# xover.net
KiCad netlist of a schematic drawn in Altium Designer
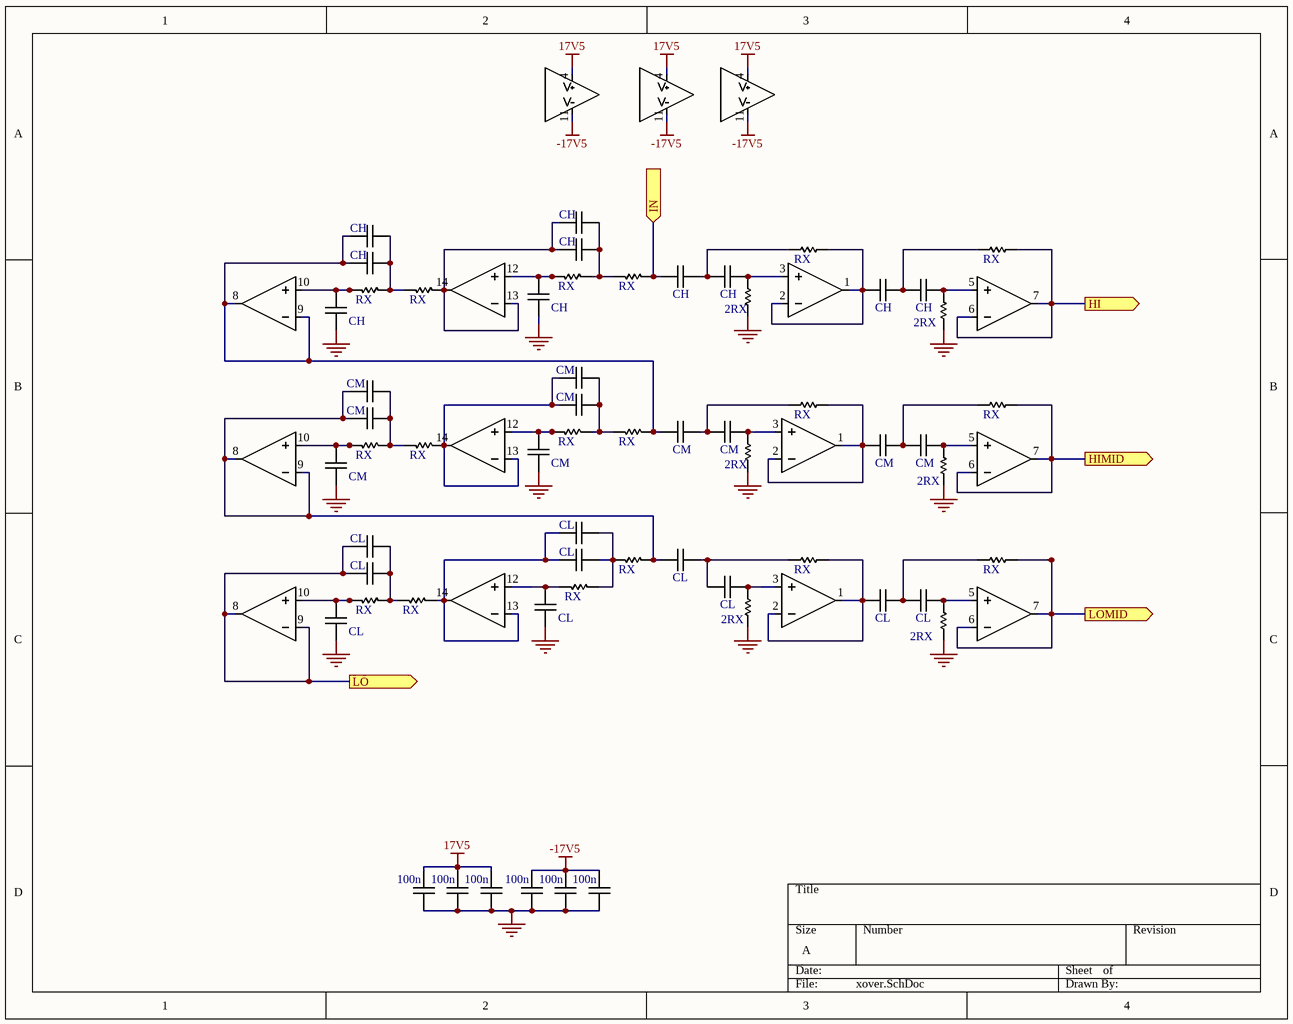
[diagram p0: xover.SchDoc]

(export (version "E")
  (design (tool "Eeschema 10.0.6"))
  (components
    (comp (ref "C136")
      (value "CH")
      (footprint "0805")
      (fields (field (name "PARTNUMBER") "NMC0805NPO562J50TRPLPF"))
      (libsource (lib "mix") (part "CAP"))
    )
    (comp (ref "C139")
      (value "CH")
      (footprint "0805")
      (fields (field (name "PARTNUMBER") "NMC0805NPO562J50TRPLPF"))
      (libsource (lib "mix") (part "CAP"))
    )
    (comp (ref "C142")
      (value "CH")
      (footprint "0805")
      (fields (field (name "PARTNUMBER") "NMC0805NPO562J50TRPLPF"))
      (libsource (lib "mix") (part "CAP"))
    )
    (comp (ref "C143")
      (value "CH")
      (footprint "0805")
      (fields (field (name "PARTNUMBER") "NMC0805NPO562J50TRPLPF"))
      (libsource (lib "mix") (part "CAP"))
    )
    (comp (ref "C145")
      (value "CH")
      (footprint "0805")
      (fields (field (name "PARTNUMBER") "NMC0805NPO562J50TRPLPF"))
      (libsource (lib "mix") (part "CAP"))
    )
    (comp (ref "C148")
      (value "CH")
      (footprint "0805")
      (fields (field (name "PARTNUMBER") "NMC0805NPO562J50TRPLPF"))
      (libsource (lib "mix") (part "CAP"))
    )
    (comp (ref "C149")
      (value "CH")
      (footprint "0805")
      (fields (field (name "PARTNUMBER") "NMC0805NPO562J50TRPLPF"))
      (libsource (lib "mix") (part "CAP"))
    )
    (comp (ref "C150")
      (value "CH")
      (footprint "0805")
      (fields (field (name "PARTNUMBER") "NMC0805NPO562J50TRPLPF"))
      (libsource (lib "mix") (part "CAP"))
    )
    (comp (ref "C152")
      (value "CH")
      (footprint "0805")
      (fields (field (name "PARTNUMBER") "NMC0805NPO562J50TRPLPF"))
      (libsource (lib "mix") (part "CAP"))
    )
    (comp (ref "C154")
      (value "CH")
      (footprint "0805")
      (fields (field (name "PARTNUMBER") "NMC0805NPO562J50TRPLPF"))
      (libsource (lib "mix") (part "CAP"))
    )
    (comp (ref "C155")
      (value "CM")
      (footprint "0805")
      (fields (field (name "PARTNUMBER") "C0805C223J5JACTU"))
      (libsource (lib "mix") (part "CAP"))
    )
    (comp (ref "C158")
      (value "CM")
      (footprint "0805")
      (fields (field (name "PARTNUMBER") "C0805C223J5JACTU"))
      (libsource (lib "mix") (part "CAP"))
    )
    (comp (ref "C162")
      (value "CM")
      (footprint "0805")
      (fields (field (name "PARTNUMBER") "C0805C223J5JACTU"))
      (libsource (lib "mix") (part "CAP"))
    )
    (comp (ref "C163")
      (value "CM")
      (footprint "0805")
      (fields (field (name "PARTNUMBER") "C0805C223J5JACTU"))
      (libsource (lib "mix") (part "CAP"))
    )
    (comp (ref "C166")
      (value "CM")
      (footprint "0805")
      (fields (field (name "PARTNUMBER") "C0805C223J5JACTU"))
      (libsource (lib "mix") (part "CAP"))
    )
    (comp (ref "C170")
      (value "CM")
      (footprint "0805")
      (fields (field (name "PARTNUMBER") "C0805C223J5JACTU"))
      (libsource (lib "mix") (part "CAP"))
    )
    (comp (ref "C171")
      (value "CM")
      (footprint "0805")
      (fields (field (name "PARTNUMBER") "C0805C223J5JACTU"))
      (libsource (lib "mix") (part "CAP"))
    )
    (comp (ref "C172")
      (value "CM")
      (footprint "0805")
      (fields (field (name "PARTNUMBER") "C0805C223J5JACTU"))
      (libsource (lib "mix") (part "CAP"))
    )
    (comp (ref "C174")
      (value "CM")
      (footprint "0805")
      (fields (field (name "PARTNUMBER") "C0805C223J5JACTU"))
      (libsource (lib "mix") (part "CAP"))
    )
    (comp (ref "C176")
      (value "CM")
      (footprint "0805")
      (fields (field (name "PARTNUMBER") "C0805C223J5JACTU"))
      (libsource (lib "mix") (part "CAP"))
    )
    (comp (ref "C180")
      (value "CL")
      (footprint "0805")
      (fields (field (name "PARTNUMBER") "NMC0805X7R823J50TRPF"))
      (libsource (lib "mix") (part "CAP"))
    )
    (comp (ref "C182")
      (value "CL")
      (footprint "0805")
      (fields (field (name "PARTNUMBER") "NMC0805X7R823J50TRPF"))
      (libsource (lib "mix") (part "CAP"))
    )
    (comp (ref "C185")
      (value "CL")
      (footprint "0805")
      (fields (field (name "PARTNUMBER") "NMC0805X7R823J50TRPF"))
      (libsource (lib "mix") (part "CAP"))
    )
    (comp (ref "C186")
      (value "CL")
      (footprint "0805")
      (fields (field (name "PARTNUMBER") "NMC0805X7R823J50TRPF"))
      (libsource (lib "mix") (part "CAP"))
    )
    (comp (ref "C188")
      (value "CL")
      (footprint "0805")
      (fields (field (name "PARTNUMBER") "NMC0805X7R823J50TRPF"))
      (libsource (lib "mix") (part "CAP"))
    )
    (comp (ref "C192")
      (value "CL")
      (footprint "0805")
      (fields (field (name "PARTNUMBER") "NMC0805X7R823J50TRPF"))
      (libsource (lib "mix") (part "CAP"))
    )
    (comp (ref "C193")
      (value "CL")
      (footprint "0805")
      (fields (field (name "PARTNUMBER") "NMC0805X7R823J50TRPF"))
      (libsource (lib "mix") (part "CAP"))
    )
    (comp (ref "C194")
      (value "CL")
      (footprint "0805")
      (fields (field (name "PARTNUMBER") "NMC0805X7R823J50TRPF"))
      (libsource (lib "mix") (part "CAP"))
    )
    (comp (ref "C198")
      (value "CL")
      (footprint "0805")
      (fields (field (name "PARTNUMBER") "NMC0805X7R823J50TRPF"))
      (libsource (lib "mix") (part "CAP"))
    )
    (comp (ref "C200")
      (value "CL")
      (footprint "0805")
      (fields (field (name "PARTNUMBER") "NMC0805X7R823J50TRPF"))
      (libsource (lib "mix") (part "CAP"))
    )
    (comp (ref "C204")
      (value "100n")
      (footprint "0805")
      (fields (field (name "PARTNUMBER") "C0805C104K1RAC7800"))
      (libsource (lib "mix") (part "CAP"))
    )
    (comp (ref "C206")
      (value "100n")
      (footprint "0805")
      (fields (field (name "PARTNUMBER") "C0805C104K1RAC7800"))
      (libsource (lib "mix") (part "CAP"))
    )
    (comp (ref "C211")
      (value "100n")
      (footprint "0805")
      (fields (field (name "PARTNUMBER") "C0805C104K1RAC7800"))
      (libsource (lib "mix") (part "CAP"))
    )
    (comp (ref "C213")
      (value "100n")
      (footprint "0805")
      (fields (field (name "PARTNUMBER") "C0805C104K1RAC7800"))
      (libsource (lib "mix") (part "CAP"))
    )
    (comp (ref "C217")
      (value "100n")
      (footprint "0805")
      (fields (field (name "PARTNUMBER") "C0805C104K1RAC7800"))
      (libsource (lib "mix") (part "CAP"))
    )
    (comp (ref "C218")
      (value "100n")
      (footprint "0805")
      (fields (field (name "PARTNUMBER") "C0805C104K1RAC7800"))
      (libsource (lib "mix") (part "CAP"))
    )
    (comp (ref "R154")
      (value "RX")
      (footprint "0805")
      (fields (field (name "PARTNUMBER") "ERJ-6ENF4871V"))
      (libsource (lib "mix") (part "RES"))
    )
    (comp (ref "R156")
      (value "RX")
      (footprint "0805")
      (fields (field (name "PARTNUMBER") "ERJ-6ENF4871V"))
      (libsource (lib "mix") (part "RES"))
    )
    (comp (ref "R158")
      (value "RX")
      (footprint "0805")
      (fields (field (name "PARTNUMBER") "ERJ-6ENF4871V"))
      (libsource (lib "mix") (part "RES"))
    )
    (comp (ref "R159")
      (value "RX")
      (footprint "0805")
      (fields (field (name "PARTNUMBER") "ERJ-6ENF4871V"))
      (libsource (lib "mix") (part "RES"))
    )
    (comp (ref "R162")
      (value "RX")
      (footprint "0805")
      (fields (field (name "PARTNUMBER") "ERJ-6ENF4871V"))
      (libsource (lib "mix") (part "RES"))
    )
    (comp (ref "R163")
      (value "RX")
      (footprint "0805")
      (fields (field (name "PARTNUMBER") "ERJ-6ENF4871V"))
      (libsource (lib "mix") (part "RES"))
    )
    (comp (ref "R165")
      (value "2RX")
      (footprint "0805")
      (fields (field (name "PARTNUMBER") "ERJ-6ENF9761V"))
      (libsource (lib "mix") (part "RES"))
    )
    (comp (ref "R167")
      (value "2RX")
      (footprint "0805")
      (fields (field (name "PARTNUMBER") "ERJ-6ENF9761V"))
      (libsource (lib "mix") (part "RES"))
    )
    (comp (ref "R169")
      (value "RX")
      (footprint "0805")
      (fields (field (name "PARTNUMBER") "ERJ-6ENF4871V"))
      (libsource (lib "mix") (part "RES"))
    )
    (comp (ref "R170")
      (value "RX")
      (footprint "0805")
      (fields (field (name "PARTNUMBER") "ERJ-6ENF4871V"))
      (libsource (lib "mix") (part "RES"))
    )
    (comp (ref "R172")
      (value "RX")
      (footprint "0805")
      (fields (field (name "PARTNUMBER") "ERJ-6ENF4871V"))
      (libsource (lib "mix") (part "RES"))
    )
    (comp (ref "R176")
      (value "RX")
      (footprint "0805")
      (fields (field (name "PARTNUMBER") "ERJ-6ENF4871V"))
      (libsource (lib "mix") (part "RES"))
    )
    (comp (ref "R180")
      (value "RX")
      (footprint "0805")
      (fields (field (name "PARTNUMBER") "ERJ-6ENF4871V"))
      (libsource (lib "mix") (part "RES"))
    )
    (comp (ref "R181")
      (value "RX")
      (footprint "0805")
      (fields (field (name "PARTNUMBER") "ERJ-6ENF4871V"))
      (libsource (lib "mix") (part "RES"))
    )
    (comp (ref "R183")
      (value "2RX")
      (footprint "0805")
      (fields (field (name "PARTNUMBER") "ERJ-6ENF9761V"))
      (libsource (lib "mix") (part "RES"))
    )
    (comp (ref "R186")
      (value "2RX")
      (footprint "0805")
      (fields (field (name "PARTNUMBER") "ERJ-6ENF9761V"))
      (libsource (lib "mix") (part "RES"))
    )
    (comp (ref "R189")
      (value "RX")
      (footprint "0805")
      (fields (field (name "PARTNUMBER") "ERJ-6ENF4871V"))
      (libsource (lib "mix") (part "RES"))
    )
    (comp (ref "R191")
      (value "RX")
      (footprint "0805")
      (fields (field (name "PARTNUMBER") "ERJ-6ENF4871V"))
      (libsource (lib "mix") (part "RES"))
    )
    (comp (ref "R194")
      (value "RX")
      (footprint "0805")
      (fields (field (name "PARTNUMBER") "ERJ-6ENF4871V"))
      (libsource (lib "mix") (part "RES"))
    )
    (comp (ref "R195")
      (value "RX")
      (footprint "0805")
      (fields (field (name "PARTNUMBER") "ERJ-6ENF4871V"))
      (libsource (lib "mix") (part "RES"))
    )
    (comp (ref "R198")
      (value "RX")
      (footprint "0805")
      (fields (field (name "PARTNUMBER") "ERJ-6ENF4871V"))
      (libsource (lib "mix") (part "RES"))
    )
    (comp (ref "R199")
      (value "RX")
      (footprint "0805")
      (fields (field (name "PARTNUMBER") "ERJ-6ENF4871V"))
      (libsource (lib "mix") (part "RES"))
    )
    (comp (ref "R203")
      (value "2RX")
      (footprint "0805")
      (fields (field (name "PARTNUMBER") "ERJ-6ENF9761V"))
      (libsource (lib "mix") (part "RES"))
    )
    (comp (ref "R205")
      (value "2RX")
      (footprint "0805")
      (fields (field (name "PARTNUMBER") "ERJ-6ENF9761V"))
      (libsource (lib "mix") (part "RES"))
    )
    (comp (ref "U27")
      (value "OPA16X4")
      (footprint "SOIC127P600X175-14M")
      (fields (field (name "PARTNUMBER") "OPA1664AIDR"))
      (libsource (lib "") (part "OPA16X4_1"))
    )
    (comp (ref "U28")
      (value "OPA16X4")
      (footprint "SOIC127P600X175-14M")
      (fields (field (name "PARTNUMBER") "OPA1664AIDR"))
      (libsource (lib "") (part "OPA16X4_1"))
    )
    (comp (ref "U29")
      (value "OPA16X4")
      (footprint "SOIC127P600X175-14M")
      (fields (field (name "PARTNUMBER") "OPA1664AIDR"))
      (libsource (lib "mix") (part "OPA16X4"))
    )
  )
  (nets
    (net (code "1") (name "-17V5") (class "Default")
      (node (ref "C204") (pin "1") (pinfunction "1_1") (pintype "passive"))
      (node (ref "C206") (pin "1") (pinfunction "1_1") (pintype "passive"))
      (node (ref "C217") (pin "1") (pinfunction "1_1") (pintype "passive"))
      (node (ref "U27") (pin "11") (pinfunction "V-_11") (pintype "passive"))
      (node (ref "U28") (pin "11") (pinfunction "V-_11") (pintype "passive"))
      (node (ref "U29") (pin "11") (pinfunction "V-_11") (pintype "passive"))
    )
    (net (code "2") (name "/HI") (class "Default")
      (node (ref "R163") (pin "1") (pinfunction "1_1") (pintype "passive"))
      (node (ref "U27") (pin "6") (pinfunction "IN_B-_6") (pintype "passive"))
      (node (ref "U27") (pin "7") (pinfunction "OUT_B_7") (pintype "passive"))
    )
    (net (code "3") (name "/HIMID") (class "Default")
      (node (ref "R181") (pin "1") (pinfunction "1_1") (pintype "passive"))
      (node (ref "U28") (pin "6") (pinfunction "IN_B-_6") (pintype "passive"))
      (node (ref "U28") (pin "7") (pinfunction "OUT_B_7") (pintype "passive"))
    )
    (net (code "4") (name "/IN") (class "Default")
      (node (ref "C142") (pin "1") (pinfunction "1_1") (pintype "passive"))
      (node (ref "R154") (pin "1") (pinfunction "1_1") (pintype "passive"))
    )
    (net (code "5") (name "/LO") (class "Default")
      (node (ref "C182") (pin "1") (pinfunction "1_1") (pintype "passive"))
      (node (ref "C188") (pin "1") (pinfunction "1_1") (pintype "passive"))
      (node (ref "U29") (pin "8") (pinfunction "OUT_C_8") (pintype "passive"))
      (node (ref "U29") (pin "9") (pinfunction "IN_C-_9") (pintype "passive"))
    )
    (net (code "6") (name "/LOMID") (class "Default")
      (node (ref "R199") (pin "1") (pinfunction "1_1") (pintype "passive"))
      (node (ref "U29") (pin "6") (pinfunction "IN_B-_6") (pintype "passive"))
      (node (ref "U29") (pin "7") (pinfunction "OUT_B_7") (pintype "passive"))
    )
    (net (code "7") (name "17V5") (class "Default")
      (node (ref "C211") (pin "1") (pinfunction "1_1") (pintype "passive"))
      (node (ref "C213") (pin "1") (pinfunction "1_1") (pintype "passive"))
      (node (ref "C218") (pin "1") (pinfunction "1_1") (pintype "passive"))
      (node (ref "U27") (pin "4") (pinfunction "V+_4") (pintype "passive"))
      (node (ref "U28") (pin "4") (pinfunction "V+_4") (pintype "passive"))
      (node (ref "U29") (pin "4") (pinfunction "V+_4") (pintype "passive"))
    )
    (net (code "8") (name "GND") (class "Default")
      (node (ref "C152") (pin "1") (pinfunction "1_1") (pintype "passive"))
      (node (ref "C154") (pin "1") (pinfunction "1_1") (pintype "passive"))
      (node (ref "C174") (pin "1") (pinfunction "1_1") (pintype "passive"))
      (node (ref "C176") (pin "1") (pinfunction "1_1") (pintype "passive"))
      (node (ref "C198") (pin "1") (pinfunction "1_1") (pintype "passive"))
      (node (ref "C200") (pin "1") (pinfunction "1_1") (pintype "passive"))
      (node (ref "C204") (pin "2") (pinfunction "2_2") (pintype "passive"))
      (node (ref "C206") (pin "2") (pinfunction "2_2") (pintype "passive"))
      (node (ref "C211") (pin "2") (pinfunction "2_2") (pintype "passive"))
      (node (ref "C213") (pin "2") (pinfunction "2_2") (pintype "passive"))
      (node (ref "C217") (pin "2") (pinfunction "2_2") (pintype "passive"))
      (node (ref "C218") (pin "2") (pinfunction "2_2") (pintype "passive"))
      (node (ref "R165") (pin "2") (pinfunction "2_2") (pintype "passive"))
      (node (ref "R167") (pin "1") (pinfunction "1_1") (pintype "passive"))
      (node (ref "R183") (pin "2") (pinfunction "2_2") (pintype "passive"))
      (node (ref "R186") (pin "1") (pinfunction "1_1") (pintype "passive"))
      (node (ref "R203") (pin "2") (pinfunction "2_2") (pintype "passive"))
      (node (ref "R205") (pin "1") (pinfunction "1_1") (pintype "passive"))
    )
    (net (code "9") (name "Net-(C136-Pad2)") (class "Default")
      (node (ref "C136") (pin "2") (pinfunction "2_2") (pintype "passive"))
      (node (ref "C143") (pin "2") (pinfunction "2_2") (pintype "passive"))
      (node (ref "R154") (pin "2") (pinfunction "2_2") (pintype "passive"))
      (node (ref "R156") (pin "1") (pinfunction "1_1") (pintype "passive"))
    )
    (net (code "10") (name "Net-(C139-Pad2)") (class "Default")
      (node (ref "C139") (pin "2") (pinfunction "2_2") (pintype "passive"))
      (node (ref "C145") (pin "2") (pinfunction "2_2") (pintype "passive"))
      (node (ref "R158") (pin "2") (pinfunction "2_2") (pintype "passive"))
      (node (ref "R159") (pin "1") (pinfunction "1_1") (pintype "passive"))
    )
    (net (code "11") (name "Net-(C142-Pad2)") (class "Default")
      (node (ref "C142") (pin "2") (pinfunction "2_2") (pintype "passive"))
      (node (ref "C148") (pin "1") (pinfunction "1_1") (pintype "passive"))
      (node (ref "R162") (pin "2") (pinfunction "2_2") (pintype "passive"))
    )
    (net (code "12") (name "Net-(C149-Pad2)") (class "Default")
      (node (ref "C149") (pin "2") (pinfunction "2_2") (pintype "passive"))
      (node (ref "C150") (pin "1") (pinfunction "1_1") (pintype "passive"))
      (node (ref "R163") (pin "2") (pinfunction "2_2") (pintype "passive"))
    )
    (net (code "13") (name "Net-(C155-Pad2)") (class "Default")
      (node (ref "C155") (pin "2") (pinfunction "2_2") (pintype "passive"))
      (node (ref "C163") (pin "2") (pinfunction "2_2") (pintype "passive"))
      (node (ref "R169") (pin "2") (pinfunction "2_2") (pintype "passive"))
      (node (ref "R172") (pin "1") (pinfunction "1_1") (pintype "passive"))
    )
    (net (code "14") (name "Net-(C158-Pad2)") (class "Default")
      (node (ref "C158") (pin "2") (pinfunction "2_2") (pintype "passive"))
      (node (ref "C166") (pin "2") (pinfunction "2_2") (pintype "passive"))
      (node (ref "R170") (pin "2") (pinfunction "2_2") (pintype "passive"))
      (node (ref "R176") (pin "1") (pinfunction "1_1") (pintype "passive"))
    )
    (net (code "15") (name "Net-(C162-Pad2)") (class "Default")
      (node (ref "C162") (pin "2") (pinfunction "2_2") (pintype "passive"))
      (node (ref "C170") (pin "1") (pinfunction "1_1") (pintype "passive"))
      (node (ref "R180") (pin "2") (pinfunction "2_2") (pintype "passive"))
    )
    (net (code "16") (name "Net-(C171-Pad2)") (class "Default")
      (node (ref "C171") (pin "2") (pinfunction "2_2") (pintype "passive"))
      (node (ref "C172") (pin "1") (pinfunction "1_1") (pintype "passive"))
      (node (ref "R181") (pin "2") (pinfunction "2_2") (pintype "passive"))
    )
    (net (code "17") (name "Net-(C180-Pad2)") (class "Default")
      (node (ref "C180") (pin "2") (pinfunction "2_2") (pintype "passive"))
      (node (ref "C186") (pin "2") (pinfunction "2_2") (pintype "passive"))
      (node (ref "R189") (pin "2") (pinfunction "2_2") (pintype "passive"))
      (node (ref "R191") (pin "1") (pinfunction "1_1") (pintype "passive"))
    )
    (net (code "18") (name "Net-(C182-Pad2)") (class "Default")
      (node (ref "C182") (pin "2") (pinfunction "2_2") (pintype "passive"))
      (node (ref "C188") (pin "2") (pinfunction "2_2") (pintype "passive"))
      (node (ref "R194") (pin "2") (pinfunction "2_2") (pintype "passive"))
      (node (ref "R195") (pin "1") (pinfunction "1_1") (pintype "passive"))
    )
    (net (code "19") (name "Net-(C185-Pad1)") (class "Default")
      (node (ref "C185") (pin "1") (pinfunction "1_1") (pintype "passive"))
      (node (ref "C192") (pin "1") (pinfunction "1_1") (pintype "passive"))
      (node (ref "R198") (pin "2") (pinfunction "2_2") (pintype "passive"))
    )
    (net (code "20") (name "Net-(C193-Pad2)") (class "Default")
      (node (ref "C193") (pin "2") (pinfunction "2_2") (pintype "passive"))
      (node (ref "C194") (pin "1") (pinfunction "1_1") (pintype "passive"))
      (node (ref "R199") (pin "2") (pinfunction "2_2") (pintype "passive"))
    )
    (net (code "21") (name "Net-(U27A-+IN_A)") (class "Default")
      (node (ref "C148") (pin "2") (pinfunction "2_2") (pintype "passive"))
      (node (ref "R167") (pin "2") (pinfunction "2_2") (pintype "passive"))
      (node (ref "U27") (pin "3") (pinfunction "+IN_A_3") (pintype "passive"))
    )
    (net (code "22") (name "Net-(U27A--IN_A)") (class "Default")
      (node (ref "C149") (pin "1") (pinfunction "1_1") (pintype "passive"))
      (node (ref "R162") (pin "1") (pinfunction "1_1") (pintype "passive"))
      (node (ref "U27") (pin "1") (pinfunction "OUT_A_1") (pintype "passive"))
      (node (ref "U27") (pin "2") (pinfunction "-IN_A_2") (pintype "passive"))
    )
    (net (code "23") (name "Net-(U27B-IN_B+)") (class "Default")
      (node (ref "C150") (pin "2") (pinfunction "2_2") (pintype "passive"))
      (node (ref "R165") (pin "1") (pinfunction "1_1") (pintype "passive"))
      (node (ref "U27") (pin "5") (pinfunction "IN_B+_5") (pintype "passive"))
    )
    (net (code "24") (name "Net-(U27C-IN_C+)") (class "Default")
      (node (ref "C154") (pin "2") (pinfunction "2_2") (pintype "passive"))
      (node (ref "R159") (pin "2") (pinfunction "2_2") (pintype "passive"))
      (node (ref "U27") (pin "10") (pinfunction "IN_C+_10") (pintype "passive"))
    )
    (net (code "25") (name "Net-(U27C-IN_C-)") (class "Default")
      (node (ref "C139") (pin "1") (pinfunction "1_1") (pintype "passive"))
      (node (ref "C145") (pin "1") (pinfunction "1_1") (pintype "passive"))
      (node (ref "C162") (pin "1") (pinfunction "1_1") (pintype "passive"))
      (node (ref "R169") (pin "1") (pinfunction "1_1") (pintype "passive"))
      (node (ref "U27") (pin "8") (pinfunction "OUT_C_8") (pintype "passive"))
      (node (ref "U27") (pin "9") (pinfunction "IN_C-_9") (pintype "passive"))
    )
    (net (code "26") (name "Net-(U27D-IN_D+)") (class "Default")
      (node (ref "C152") (pin "2") (pinfunction "2_2") (pintype "passive"))
      (node (ref "R156") (pin "2") (pinfunction "2_2") (pintype "passive"))
      (node (ref "U27") (pin "12") (pinfunction "IN_D+_12") (pintype "passive"))
    )
    (net (code "27") (name "Net-(U27D-IN_D-)") (class "Default")
      (node (ref "C136") (pin "1") (pinfunction "1_1") (pintype "passive"))
      (node (ref "C143") (pin "1") (pinfunction "1_1") (pintype "passive"))
      (node (ref "R158") (pin "1") (pinfunction "1_1") (pintype "passive"))
      (node (ref "U27") (pin "13") (pinfunction "IN_D-_13") (pintype "passive"))
      (node (ref "U27") (pin "14") (pinfunction "OUT_D_14") (pintype "passive"))
    )
    (net (code "28") (name "Net-(U28A-+IN_A)") (class "Default")
      (node (ref "C170") (pin "2") (pinfunction "2_2") (pintype "passive"))
      (node (ref "R186") (pin "2") (pinfunction "2_2") (pintype "passive"))
      (node (ref "U28") (pin "3") (pinfunction "+IN_A_3") (pintype "passive"))
    )
    (net (code "29") (name "Net-(U28A--IN_A)") (class "Default")
      (node (ref "C171") (pin "1") (pinfunction "1_1") (pintype "passive"))
      (node (ref "R180") (pin "1") (pinfunction "1_1") (pintype "passive"))
      (node (ref "U28") (pin "1") (pinfunction "OUT_A_1") (pintype "passive"))
      (node (ref "U28") (pin "2") (pinfunction "-IN_A_2") (pintype "passive"))
    )
    (net (code "30") (name "Net-(U28B-IN_B+)") (class "Default")
      (node (ref "C172") (pin "2") (pinfunction "2_2") (pintype "passive"))
      (node (ref "R183") (pin "1") (pinfunction "1_1") (pintype "passive"))
      (node (ref "U28") (pin "5") (pinfunction "IN_B+_5") (pintype "passive"))
    )
    (net (code "31") (name "Net-(U28C-IN_C+)") (class "Default")
      (node (ref "C176") (pin "2") (pinfunction "2_2") (pintype "passive"))
      (node (ref "R176") (pin "2") (pinfunction "2_2") (pintype "passive"))
      (node (ref "U28") (pin "10") (pinfunction "IN_C+_10") (pintype "passive"))
    )
    (net (code "32") (name "Net-(U28C-IN_C-)") (class "Default")
      (node (ref "C158") (pin "1") (pinfunction "1_1") (pintype "passive"))
      (node (ref "C166") (pin "1") (pinfunction "1_1") (pintype "passive"))
      (node (ref "C185") (pin "2") (pinfunction "2_2") (pintype "passive"))
      (node (ref "R189") (pin "1") (pinfunction "1_1") (pintype "passive"))
      (node (ref "U28") (pin "8") (pinfunction "OUT_C_8") (pintype "passive"))
      (node (ref "U28") (pin "9") (pinfunction "IN_C-_9") (pintype "passive"))
    )
    (net (code "33") (name "Net-(U28D-IN_D+)") (class "Default")
      (node (ref "C174") (pin "2") (pinfunction "2_2") (pintype "passive"))
      (node (ref "R172") (pin "2") (pinfunction "2_2") (pintype "passive"))
      (node (ref "U28") (pin "12") (pinfunction "IN_D+_12") (pintype "passive"))
    )
    (net (code "34") (name "Net-(U28D-IN_D-)") (class "Default")
      (node (ref "C155") (pin "1") (pinfunction "1_1") (pintype "passive"))
      (node (ref "C163") (pin "1") (pinfunction "1_1") (pintype "passive"))
      (node (ref "R170") (pin "1") (pinfunction "1_1") (pintype "passive"))
      (node (ref "U28") (pin "13") (pinfunction "IN_D-_13") (pintype "passive"))
      (node (ref "U28") (pin "14") (pinfunction "OUT_D_14") (pintype "passive"))
    )
    (net (code "35") (name "Net-(U29A-+IN_A)") (class "Default")
      (node (ref "C192") (pin "2") (pinfunction "2_2") (pintype "passive"))
      (node (ref "R205") (pin "2") (pinfunction "2_2") (pintype "passive"))
      (node (ref "U29") (pin "3") (pinfunction "+IN_A_3") (pintype "passive"))
    )
    (net (code "36") (name "Net-(U29A--IN_A)") (class "Default")
      (node (ref "C193") (pin "1") (pinfunction "1_1") (pintype "passive"))
      (node (ref "R198") (pin "1") (pinfunction "1_1") (pintype "passive"))
      (node (ref "U29") (pin "1") (pinfunction "OUT_A_1") (pintype "passive"))
      (node (ref "U29") (pin "2") (pinfunction "-IN_A_2") (pintype "passive"))
    )
    (net (code "37") (name "Net-(U29B-IN_B+)") (class "Default")
      (node (ref "C194") (pin "2") (pinfunction "2_2") (pintype "passive"))
      (node (ref "R203") (pin "1") (pinfunction "1_1") (pintype "passive"))
      (node (ref "U29") (pin "5") (pinfunction "IN_B+_5") (pintype "passive"))
    )
    (net (code "38") (name "Net-(U29C-IN_C+)") (class "Default")
      (node (ref "C200") (pin "2") (pinfunction "2_2") (pintype "passive"))
      (node (ref "R195") (pin "2") (pinfunction "2_2") (pintype "passive"))
      (node (ref "U29") (pin "10") (pinfunction "IN_C+_10") (pintype "passive"))
    )
    (net (code "39") (name "Net-(U29D-IN_D+)") (class "Default")
      (node (ref "C198") (pin "2") (pinfunction "2_2") (pintype "passive"))
      (node (ref "R191") (pin "2") (pinfunction "2_2") (pintype "passive"))
      (node (ref "U29") (pin "12") (pinfunction "IN_D+_12") (pintype "passive"))
    )
    (net (code "40") (name "Net-(U29D-IN_D-)") (class "Default")
      (node (ref "C180") (pin "1") (pinfunction "1_1") (pintype "passive"))
      (node (ref "C186") (pin "1") (pinfunction "1_1") (pintype "passive"))
      (node (ref "R194") (pin "1") (pinfunction "1_1") (pintype "passive"))
      (node (ref "U29") (pin "13") (pinfunction "IN_D-_13") (pintype "passive"))
      (node (ref "U29") (pin "14") (pinfunction "OUT_D_14") (pintype "passive"))
    )
  )
)
